# ea_rpi_modul.net
KiCad netlist of a schematic drawn in EAGLE
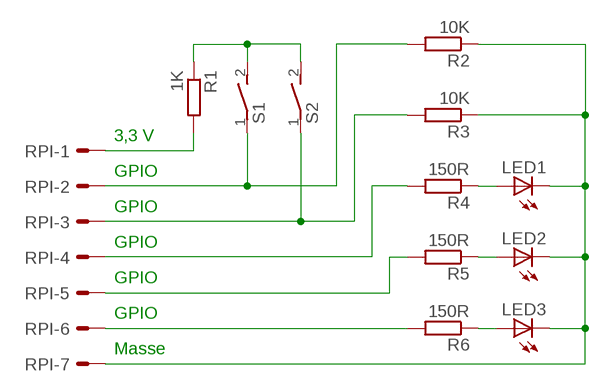
[diagram p0: schematic, sheet 1]

(export (version "E")
  (design (tool "Eeschema 10.0.6"))
  (components
    (comp (ref "LED1")
      (value "LED5MM")
      (footprint "eagle-import:LED5MM")
      (libsource (lib "eagle-import") (part "LED5MM"))
    )
    (comp (ref "LED2")
      (value "LED5MM")
      (footprint "eagle-import:LED5MM")
      (libsource (lib "eagle-import") (part "LED5MM"))
    )
    (comp (ref "LED3")
      (value "LED5MM")
      (footprint "eagle-import:LED5MM")
      (libsource (lib "eagle-import") (part "LED5MM"))
    )
    (comp (ref "R1")
      (value "1K")
      (footprint "eagle-import:0617_22")
      (libsource (lib "eagle-import") (part "R-EU_0617/22"))
    )
    (comp (ref "R2")
      (value "10K")
      (footprint "eagle-import:0617_22")
      (libsource (lib "eagle-import") (part "R-EU_0617/22"))
    )
    (comp (ref "R3")
      (value "10K")
      (footprint "eagle-import:0617_22")
      (libsource (lib "eagle-import") (part "R-EU_0617/22"))
    )
    (comp (ref "R4")
      (value "150R")
      (footprint "eagle-import:0617_22")
      (libsource (lib "eagle-import") (part "R-EU_0617/22"))
    )
    (comp (ref "R5")
      (value "150R")
      (footprint "eagle-import:0617_22")
      (libsource (lib "eagle-import") (part "R-EU_0617/22"))
    )
    (comp (ref "R6")
      (value "150R")
      (footprint "eagle-import:0617_22")
      (libsource (lib "eagle-import") (part "R-EU_0617/22"))
    )
    (comp (ref "RPI")
      (value "ML40LE")
      (footprint "eagle-import:ML40L")
      (libsource (lib "eagle-import") (part "ML40LE"))
    )
    (comp (ref "S1")
      (value "DS01E")
      (footprint "eagle-import:DS-01")
      (libsource (lib "eagle-import") (part "DS01E"))
    )
    (comp (ref "S2")
      (value "DS01E")
      (footprint "eagle-import:DS-01")
      (libsource (lib "eagle-import") (part "DS01E"))
    )
  )
  (nets
    (net (code "1") (name "Net-(LED1-C)") (class "Default")
      (node (ref "LED1") (pin "K") (pinfunction "C_K") (pintype "passive"))
      (node (ref "LED2") (pin "K") (pinfunction "C_K") (pintype "passive"))
      (node (ref "LED3") (pin "K") (pinfunction "C_K") (pintype "passive"))
      (node (ref "R2") (pin "1") (pinfunction "1_1") (pintype "passive"))
      (node (ref "R3") (pin "1") (pinfunction "1_1") (pintype "passive"))
      (node (ref "RPI") (pin "7") (pinfunction "S_7") (pintype "passive"))
    )
    (net (code "2") (name "Net-(LED1-PadA)") (class "Default")
      (node (ref "LED1") (pin "A") (pinfunction "A_A") (pintype "passive"))
      (node (ref "R4") (pin "1") (pinfunction "1_1") (pintype "passive"))
    )
    (net (code "3") (name "Net-(LED2-PadA)") (class "Default")
      (node (ref "LED2") (pin "A") (pinfunction "A_A") (pintype "passive"))
      (node (ref "R5") (pin "1") (pinfunction "1_1") (pintype "passive"))
    )
    (net (code "4") (name "Net-(LED3-PadA)") (class "Default")
      (node (ref "LED3") (pin "A") (pinfunction "A_A") (pintype "passive"))
      (node (ref "R6") (pin "1") (pinfunction "1_1") (pintype "passive"))
    )
    (net (code "5") (name "Net-(R1-Pad1)") (class "Default")
      (node (ref "R1") (pin "1") (pinfunction "1_1") (pintype "passive"))
      (node (ref "S1") (pin "2") (pinfunction "2_2") (pintype "passive"))
      (node (ref "S2") (pin "2") (pinfunction "2_2") (pintype "passive"))
    )
    (net (code "6") (name "Net-(RPIA-S)") (class "Default")
      (node (ref "R1") (pin "2") (pinfunction "2_2") (pintype "passive"))
      (node (ref "RPI") (pin "1") (pinfunction "S_1") (pintype "passive"))
    )
    (net (code "7") (name "Net-(RPIAH-S)") (class "Default")
      (node (ref "R4") (pin "2") (pinfunction "2_2") (pintype "passive"))
      (node (ref "RPI") (pin "4") (pinfunction "S_4") (pintype "passive"))
    )
    (net (code "8") (name "Net-(RPIAJ-S)") (class "Default")
      (node (ref "R5") (pin "2") (pinfunction "2_2") (pintype "passive"))
      (node (ref "RPI") (pin "5") (pinfunction "S_5") (pintype "passive"))
    )
    (net (code "9") (name "Net-(RPIAK-S)") (class "Default")
      (node (ref "R6") (pin "2") (pinfunction "2_2") (pintype "passive"))
      (node (ref "RPI") (pin "6") (pinfunction "S_6") (pintype "passive"))
    )
    (net (code "10") (name "Net-(RPIL-S)") (class "Default")
      (node (ref "R2") (pin "2") (pinfunction "2_2") (pintype "passive"))
      (node (ref "RPI") (pin "2") (pinfunction "S_2") (pintype "passive"))
      (node (ref "S1") (pin "1") (pinfunction "1_1") (pintype "passive"))
    )
    (net (code "11") (name "Net-(RPIW-S)") (class "Default")
      (node (ref "R3") (pin "2") (pinfunction "2_2") (pintype "passive"))
      (node (ref "RPI") (pin "3") (pinfunction "S_3") (pintype "passive"))
      (node (ref "S2") (pin "1") (pinfunction "1_1") (pintype "passive"))
    )
  )
)
